# Sensors.net
KiCad netlist of a schematic drawn in Altium Designer
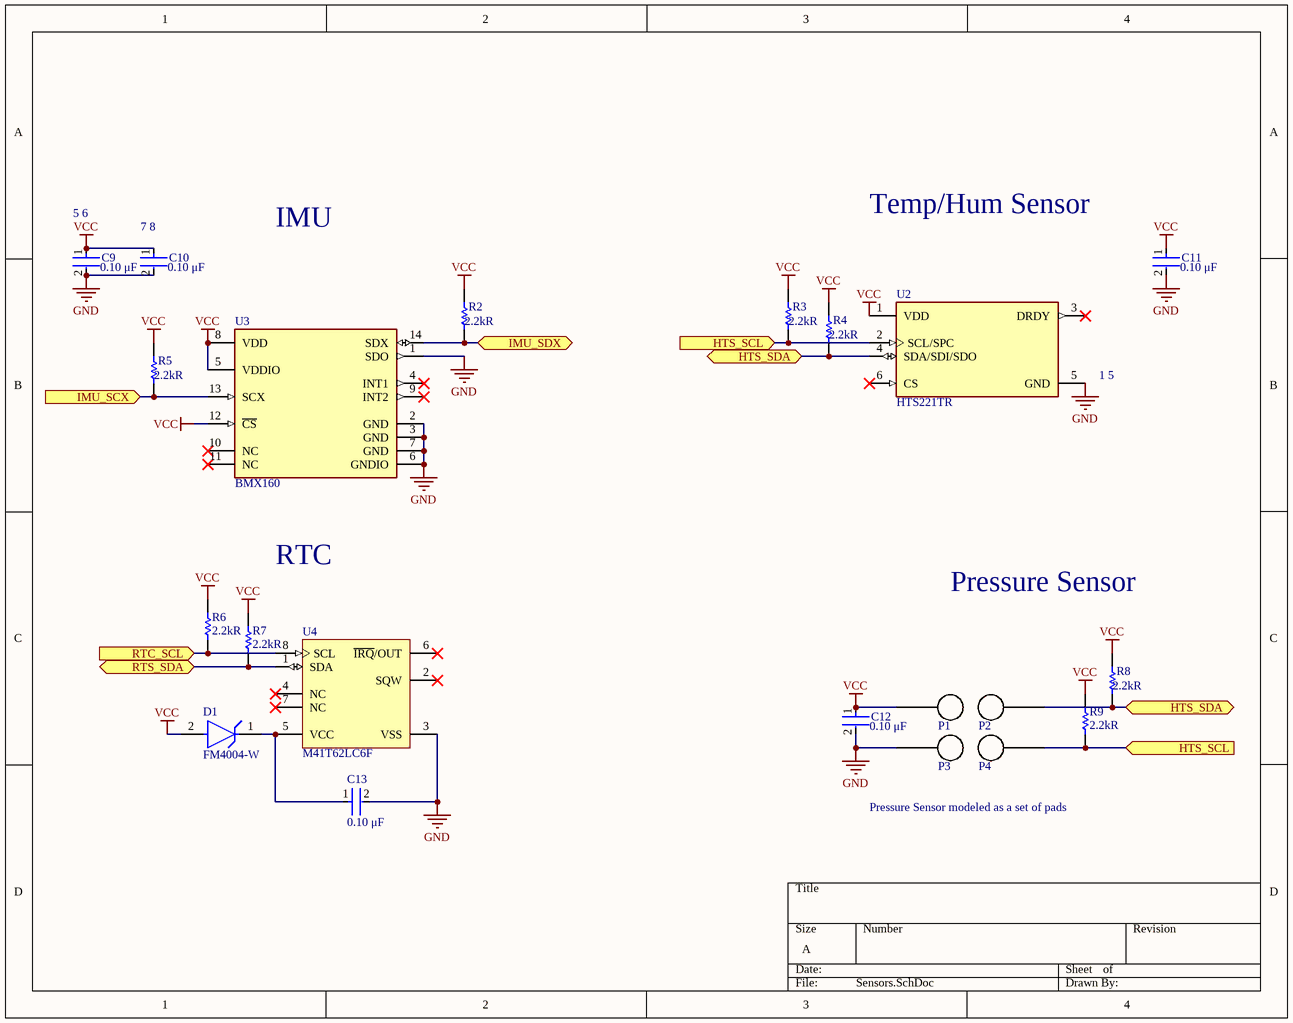
[diagram p0: Sensors.SchDoc]

(export (version "E")
  (design (tool "Eeschema 10.0.6"))
  (components
    (comp (ref "C9")
      (value "C0603C104K5RACTU")
      (footprint "FP-C0603C-CF-MFG")
      (description "CAP CER 0.1UF 50V X7R 0603")
      (fields
        (field (name "TOLERANCE") "0.1")
        (field (name "MANUFACTURER") "KEMET")
        (field (name "CAPACITANCE") "0.10 μF")
      )
      (libsource (lib "Altium Content Vault") (part "b4654b650e69147ec39a6b967a45e02"))
    )
    (comp (ref "C10")
      (value "C0603C104K5RACTU")
      (footprint "FP-C0603C-CF-MFG")
      (description "CAP CER 0.1UF 50V X7R 0603")
      (fields
        (field (name "TOLERANCE") "0.1")
        (field (name "MANUFACTURER") "KEMET")
        (field (name "CAPACITANCE") "0.10 μF")
      )
      (libsource (lib "Altium Content Vault") (part "b4654b650e69147ec39a6b967a45e02"))
    )
    (comp (ref "C11")
      (value "C0603C104K5RACTU")
      (footprint "FP-C0603C-CF-MFG")
      (description "CAP CER 0.1UF 50V X7R 0603")
      (fields
        (field (name "TOLERANCE") "0.1")
        (field (name "MANUFACTURER") "KEMET")
        (field (name "CAPACITANCE") "0.10 μF")
      )
      (libsource (lib "Altium Content Vault") (part "b4654b650e69147ec39a6b967a45e02"))
    )
    (comp (ref "C12")
      (value "C0603C104K5RACTU")
      (footprint "FP-C0603C-CF-MFG")
      (description "CAP CER 0.1UF 50V X7R 0603")
      (fields
        (field (name "TOLERANCE") "0.1")
        (field (name "MANUFACTURER") "KEMET")
        (field (name "CAPACITANCE") "0.10 μF")
      )
      (libsource (lib "Altium Content Vault") (part "b4654b650e69147ec39a6b967a45e02"))
    )
    (comp (ref "C13")
      (value "C0603C104K5RACTU")
      (footprint "FP-C0603C-CF-MFG")
      (description "CAP CER 0.1UF 50V X7R 0603")
      (fields
        (field (name "TOLERANCE") "0.1")
        (field (name "MANUFACTURER") "KEMET")
        (field (name "CAPACITANCE") "0.10 μF")
      )
      (libsource (lib "Altium Content Vault") (part "b4654b650e69147ec39a6b967a45e02"))
    )
    (comp (ref "D1")
      (value "FM4004-W")
      (footprint "FP-SMA-MFG")
      (description "TVS DIODE 5V 13.4V SMA")
      (fields
        (field (name "MANUFACTURER PART NUMBER") "SMAJ5.0A-TR")
        (field (name "MANUFACTURER") "STMicroelectronics")
      )
      (libsource (lib "Altium Content Vault") (part "7ddec9f632b8482e96f7745d0fbdf39"))
    )
    (comp (ref "P1") (value "BlankPad") (footprint "BlankPad") (libsource (lib "BlankPad") (part "BlankPad")))
    (comp (ref "P2") (value "BlankPad") (footprint "BlankPad") (libsource (lib "BlankPad") (part "BlankPad")))
    (comp (ref "P3") (value "BlankPad") (footprint "BlankPad") (libsource (lib "BlankPad") (part "BlankPad")))
    (comp (ref "P4") (value "BlankPad") (footprint "BlankPad") (libsource (lib "BlankPad") (part "BlankPad")))
    (comp (ref "R2")
      (value "ERA6AEB222V")
      (footprint "RESC2013X60X40LL20T25")
      (fields (field (name "MANUFACTURER") "Panasonic") (field (name "RESISTANCE") "2.2kR"))
      (libsource (lib "Altium Content Vault") (part "RES"))
    )
    (comp (ref "R3")
      (value "ERA6AEB222V")
      (footprint "RESC2013X60X40LL20T25")
      (fields (field (name "MANUFACTURER") "Panasonic") (field (name "RESISTANCE") "2.2kR"))
      (libsource (lib "Altium Content Vault") (part "RES"))
    )
    (comp (ref "R4")
      (value "ERA6AEB222V")
      (footprint "RESC2013X60X40LL20T25")
      (fields (field (name "MANUFACTURER") "Panasonic") (field (name "RESISTANCE") "2.2kR"))
      (libsource (lib "Altium Content Vault") (part "RES"))
    )
    (comp (ref "R5")
      (value "ERA6AEB222V")
      (footprint "RESC2013X60X40LL20T25")
      (fields (field (name "MANUFACTURER") "Panasonic") (field (name "RESISTANCE") "2.2kR"))
      (libsource (lib "Altium Content Vault") (part "RES"))
    )
    (comp (ref "R6")
      (value "ERA6AEB222V")
      (footprint "RESC2013X60X40LL20T25")
      (fields (field (name "MANUFACTURER") "Panasonic") (field (name "RESISTANCE") "2.2kR"))
      (libsource (lib "Altium Content Vault") (part "RES"))
    )
    (comp (ref "R7")
      (value "ERA6AEB222V")
      (footprint "RESC2013X60X40LL20T25")
      (fields (field (name "MANUFACTURER") "Panasonic") (field (name "RESISTANCE") "2.2kR"))
      (libsource (lib "Altium Content Vault") (part "RES"))
    )
    (comp (ref "R8")
      (value "ERA6AEB222V")
      (footprint "RESC2013X60X40LL20T25")
      (fields (field (name "MANUFACTURER") "Panasonic") (field (name "RESISTANCE") "2.2kR"))
      (libsource (lib "Altium Content Vault") (part "RES"))
    )
    (comp (ref "R9")
      (value "ERA6AEB222V")
      (footprint "RESC2013X60X40LL20T25")
      (fields (field (name "MANUFACTURER") "Panasonic") (field (name "RESISTANCE") "2.2kR"))
      (libsource (lib "Altium Content Vault") (part "RES"))
    )
    (comp (ref "U2")
      (value "HTS221TR")
      (footprint "FP-HTS221TR-MFG")
      (description "SENS HUMI/TEMP 2.5V I2C 4.5% SMD")
      (libsource (lib "Altium Content Vault") (part "2053849febfc3e541f8558c6e004e7c"))
    )
    (comp (ref "U3")
      (value "BMX160")
      (footprint "FP-BMX160-MFG")
      (description "IMU ACCEL/GYRO")
      (libsource (lib "Altium Content Vault") (part "556c68dd7461ccc8fb75c98b9c94630"))
    )
    (comp (ref "U4")
      (value "M41T62LC6F")
      (footprint "STM-LCC8_V")
      (fields (field (name "MANUFACTURER") "STMicroelectronics"))
      (libsource (lib "Altium Content Vault") (part "STM-M41T62-LCC8"))
    )
  )
  (nets
    (net (code "1") (name "/HTS_SCL") (class "Default")
      (node (ref "R3") (pin "1") (pinfunction "1_1") (pintype "passive"))
      (node (ref "R9") (pin "1") (pinfunction "1_1") (pintype "passive"))
      (node (ref "U2") (pin "2") (pinfunction "SCL/SPC_2") (pintype "input"))
    )
    (net (code "2") (name "/HTS_SDA") (class "Default")
      (node (ref "R4") (pin "1") (pinfunction "1_1") (pintype "passive"))
      (node (ref "R8") (pin "1") (pinfunction "1_1") (pintype "passive"))
      (node (ref "U2") (pin "4") (pinfunction "SDA/SDI/SDO_4") (pintype "bidirectional"))
    )
    (net (code "3") (name "/IMU_SCX") (class "Default")
      (node (ref "R5") (pin "1") (pinfunction "1_1") (pintype "passive"))
      (node (ref "U3") (pin "13") (pinfunction "SCX_13") (pintype "input"))
    )
    (net (code "4") (name "/IMU_SDX") (class "Default")
      (node (ref "R2") (pin "1") (pinfunction "1_1") (pintype "passive"))
      (node (ref "U3") (pin "14") (pinfunction "SDX_14") (pintype "bidirectional"))
    )
    (net (code "5") (name "/RTC_SCL") (class "Default")
      (node (ref "R6") (pin "1") (pinfunction "1_1") (pintype "passive"))
      (node (ref "U4") (pin "8") (pinfunction "SCL_8") (pintype "input"))
    )
    (net (code "6") (name "/RTS_SDA") (class "Default")
      (node (ref "R7") (pin "1") (pinfunction "1_1") (pintype "passive"))
      (node (ref "U4") (pin "1") (pinfunction "SDA_1") (pintype "bidirectional"))
    )
    (net (code "7") (name "GND") (class "Default")
      (node (ref "C10") (pin "2") (pinfunction "2_2") (pintype "passive"))
      (node (ref "C11") (pin "2") (pinfunction "2_2") (pintype "passive"))
      (node (ref "C12") (pin "2") (pinfunction "2_2") (pintype "passive"))
      (node (ref "C13") (pin "2") (pinfunction "2_2") (pintype "passive"))
      (node (ref "C9") (pin "2") (pinfunction "2_2") (pintype "passive"))
      (node (ref "U2") (pin "5") (pinfunction "GND_5") (pintype "power_in"))
      (node (ref "U3") (pin "1") (pinfunction "SDO_1") (pintype "output"))
      (node (ref "U3") (pin "2") (pinfunction "GND_2") (pintype "power_in"))
      (node (ref "U3") (pin "3") (pinfunction "GND_3") (pintype "power_in"))
      (node (ref "U3") (pin "6") (pinfunction "GNDIO_6") (pintype "power_in"))
      (node (ref "U3") (pin "7") (pinfunction "GND_7") (pintype "power_in"))
      (node (ref "U4") (pin "3") (pinfunction "VSS_3") (pintype "power_in"))
    )
    (net (code "8") (name "Net-(D1-K)") (class "Default")
      (node (ref "C13") (pin "1") (pinfunction "1_1") (pintype "passive"))
      (node (ref "D1") (pin "1") (pinfunction "K_1") (pintype "passive"))
      (node (ref "U4") (pin "5") (pinfunction "VCC_5") (pintype "power_in"))
    )
    (net (code "9") (name "VCC") (class "Default")
      (node (ref "C10") (pin "1") (pinfunction "1_1") (pintype "passive"))
      (node (ref "C11") (pin "1") (pinfunction "1_1") (pintype "passive"))
      (node (ref "C12") (pin "1") (pinfunction "1_1") (pintype "passive"))
      (node (ref "C9") (pin "1") (pinfunction "1_1") (pintype "passive"))
      (node (ref "D1") (pin "2") (pinfunction "A_2") (pintype "passive"))
      (node (ref "R2") (pin "2") (pinfunction "2_2") (pintype "passive"))
      (node (ref "R3") (pin "2") (pinfunction "2_2") (pintype "passive"))
      (node (ref "R4") (pin "2") (pinfunction "2_2") (pintype "passive"))
      (node (ref "R5") (pin "2") (pinfunction "2_2") (pintype "passive"))
      (node (ref "R6") (pin "2") (pinfunction "2_2") (pintype "passive"))
      (node (ref "R7") (pin "2") (pinfunction "2_2") (pintype "passive"))
      (node (ref "R8") (pin "2") (pinfunction "2_2") (pintype "passive"))
      (node (ref "R9") (pin "2") (pinfunction "2_2") (pintype "passive"))
      (node (ref "U2") (pin "1") (pinfunction "VDD_1") (pintype "power_in"))
      (node (ref "U3") (pin "12") (pinfunction "~{CS}_12") (pintype "input"))
      (node (ref "U3") (pin "5") (pinfunction "VDDIO_5") (pintype "power_in"))
      (node (ref "U3") (pin "8") (pinfunction "VDD_8") (pintype "power_in"))
    )
    (net (code "10") (name "unconnected-(P1-Pad0)") (class "Default")
      (node (ref "P1") (pin "0") (pinfunction "0_0") (pintype "passive"))
    )
    (net (code "11") (name "unconnected-(P2-Pad0)") (class "Default")
      (node (ref "P2") (pin "0") (pinfunction "0_0") (pintype "passive"))
    )
    (net (code "12") (name "unconnected-(P3-Pad0)") (class "Default")
      (node (ref "P3") (pin "0") (pinfunction "0_0") (pintype "passive"))
    )
    (net (code "13") (name "unconnected-(P4-Pad0)") (class "Default")
      (node (ref "P4") (pin "0") (pinfunction "0_0") (pintype "passive"))
    )
    (net (code "14") (name "unconnected-(U2-CS-Pad6)") (class "Default")
      (node (ref "U2") (pin "6") (pinfunction "CS_6") (pintype "input+no_connect"))
    )
    (net (code "15") (name "unconnected-(U2-DRDY-Pad3)") (class "Default")
      (node (ref "U2") (pin "3") (pinfunction "DRDY_3") (pintype "output+no_connect"))
    )
    (net (code "16") (name "unconnected-(U3-INT1-Pad4)") (class "Default")
      (node (ref "U3") (pin "4") (pinfunction "INT1_4") (pintype "output+no_connect"))
    )
    (net (code "17") (name "unconnected-(U3-INT2-Pad9)") (class "Default")
      (node (ref "U3") (pin "9") (pinfunction "INT2_9") (pintype "output+no_connect"))
    )
    (net (code "18") (name "unconnected-(U3-NC-Pad10)") (class "Default")
      (node (ref "U3") (pin "10") (pinfunction "NC_10") (pintype "passive+no_connect"))
    )
    (net (code "19") (name "unconnected-(U3-NC-Pad11)") (class "Default")
      (node (ref "U3") (pin "11") (pinfunction "NC_11") (pintype "passive+no_connect"))
    )
    (net (code "20") (name "unconnected-(U4-NC-Pad4)") (class "Default")
      (node (ref "U4") (pin "4") (pinfunction "NC_4") (pintype "passive+no_connect"))
    )
    (net (code "21") (name "unconnected-(U4-NC-Pad7)") (class "Default")
      (node (ref "U4") (pin "7") (pinfunction "NC_7") (pintype "passive+no_connect"))
    )
    (net (code "22") (name "unconnected-(U4-SQW-Pad2)") (class "Default")
      (node (ref "U4") (pin "2") (pinfunction "SQW_2") (pintype "passive+no_connect"))
    )
    (net (code "23") (name "unconnected-(U4-~{IRQ}{slash}OUT-Pad6)") (class "Default")
      (node (ref "U4") (pin "6") (pinfunction "~{IRQ}/OUT_6") (pintype "passive+no_connect"))
    )
  )
)
